# 5V_out_driver.net
KiCad netlist of a schematic drawn in Altium Designer
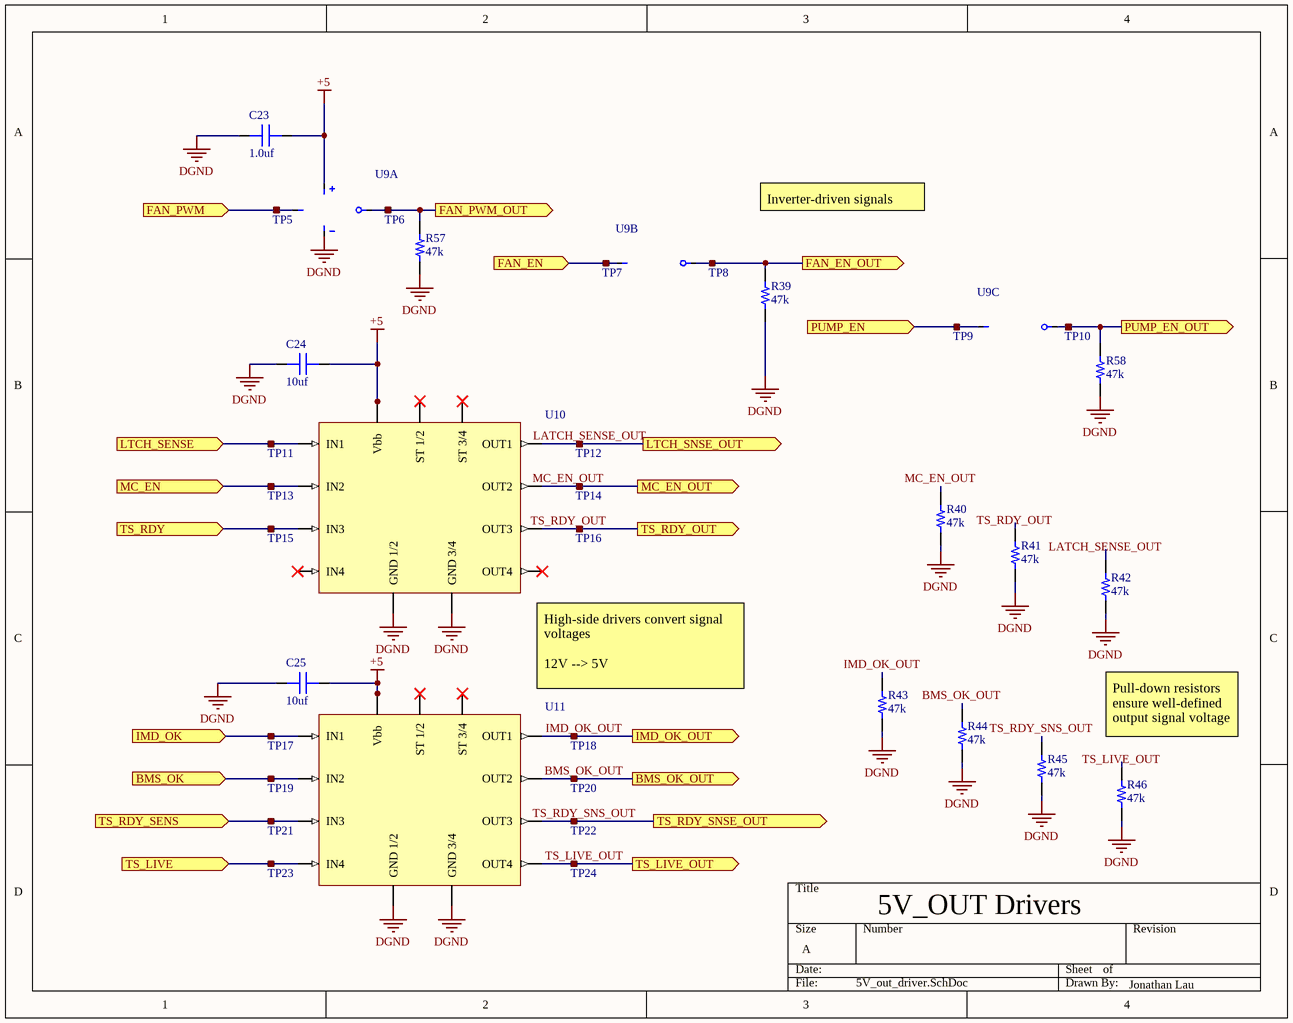
[diagram p0: 5V_out_driver.SchDoc]

(export (version "E")
  (design (tool "Eeschema 10.0.6"))
  (components
    (comp (ref "C23")
      (value "1.0uf")
      (footprint "CAP 0603/1608")
      (fields
        (field (name "Comment") "Capacitor MLCC 1.0uf 16V CAP 0603/1608")
        (field (name "CREATED_BY") "Nick Mah")
      )
      (libsource (lib "Altium-Lib") (part "Capacitor"))
    )
    (comp (ref "C24")
      (value "10uf")
      (footprint "CAP 0603/1608")
      (fields
        (field (name "Comment") "Capacitor MLCC 10uf 16V CAP 0603/1608")
        (field (name "CREATED_BY") "Nick Mah")
      )
      (libsource (lib "Altium-Lib") (part "Capacitor"))
    )
    (comp (ref "C25")
      (value "10uf")
      (footprint "CAP 0603/1608")
      (fields
        (field (name "Comment") "Capacitor MLCC 10uf 16V CAP 0603/1608")
        (field (name "CREATED_BY") "Nick Mah")
      )
      (libsource (lib "Altium-Lib") (part "Capacitor"))
    )
    (comp (ref "R39")
      (value "47k")
      (footprint "RES 0805/2012")
      (fields
        (field (name "TOLERANCE") "5%")
        (field (name "POWER") "1/4W")
        (field (name "Comment") "Resistor 47k 0805 1/4W 5%")
        (field (name "CREATED_BY") "Nick Mah")
      )
      (libsource (lib "Altium-Lib") (part "Resistor"))
    )
    (comp (ref "R40")
      (value "47k")
      (footprint "RES 0805/2012")
      (fields
        (field (name "TOLERANCE") "5%")
        (field (name "POWER") "1/4W")
        (field (name "Comment") "Resistor 47k 0805 1/4W 5%")
        (field (name "CREATED_BY") "Nick Mah")
      )
      (libsource (lib "Altium-Lib") (part "Resistor"))
    )
    (comp (ref "R41")
      (value "47k")
      (footprint "RES 0805/2012")
      (fields
        (field (name "TOLERANCE") "5%")
        (field (name "POWER") "1/4W")
        (field (name "Comment") "Resistor 47k 0805 1/4W 5%")
        (field (name "CREATED_BY") "Nick Mah")
      )
      (libsource (lib "Altium-Lib") (part "Resistor"))
    )
    (comp (ref "R42")
      (value "47k")
      (footprint "RES 0805/2012")
      (fields
        (field (name "TOLERANCE") "5%")
        (field (name "POWER") "1/4W")
        (field (name "Comment") "Resistor 47k 0805 1/4W 5%")
        (field (name "CREATED_BY") "Nick Mah")
      )
      (libsource (lib "Altium-Lib") (part "Resistor"))
    )
    (comp (ref "R43")
      (value "47k")
      (footprint "RES 0805/2012")
      (fields
        (field (name "TOLERANCE") "5%")
        (field (name "POWER") "1/4W")
        (field (name "Comment") "Resistor 47k 0805 1/4W 5%")
        (field (name "CREATED_BY") "Nick Mah")
      )
      (libsource (lib "Altium-Lib") (part "Resistor"))
    )
    (comp (ref "R44")
      (value "47k")
      (footprint "RES 0805/2012")
      (fields
        (field (name "TOLERANCE") "5%")
        (field (name "POWER") "1/4W")
        (field (name "Comment") "Resistor 47k 0805 1/4W 5%")
        (field (name "CREATED_BY") "Nick Mah")
      )
      (libsource (lib "Altium-Lib") (part "Resistor"))
    )
    (comp (ref "R45")
      (value "47k")
      (footprint "RES 0805/2012")
      (fields
        (field (name "TOLERANCE") "5%")
        (field (name "POWER") "1/4W")
        (field (name "Comment") "Resistor 47k 0805 1/4W 5%")
        (field (name "CREATED_BY") "Nick Mah")
      )
      (libsource (lib "Altium-Lib") (part "Resistor"))
    )
    (comp (ref "R46")
      (value "47k")
      (footprint "RES 0805/2012")
      (fields
        (field (name "TOLERANCE") "5%")
        (field (name "POWER") "1/4W")
        (field (name "Comment") "Resistor 47k 0805 1/4W 5%")
        (field (name "CREATED_BY") "Nick Mah")
      )
      (libsource (lib "Altium-Lib") (part "Resistor"))
    )
    (comp (ref "R57")
      (value "47k")
      (footprint "RES 0805/2012")
      (fields
        (field (name "TOLERANCE") "5%")
        (field (name "POWER") "1/4W")
        (field (name "Comment") "Resistor 47k 0805 1/4W 5%")
        (field (name "CREATED_BY") "Nick Mah")
      )
      (libsource (lib "Altium-Lib") (part "Resistor"))
    )
    (comp (ref "R58")
      (value "47k")
      (footprint "RES 0805/2012")
      (fields
        (field (name "TOLERANCE") "5%")
        (field (name "POWER") "1/4W")
        (field (name "Comment") "Resistor 47k 0805 1/4W 5%")
        (field (name "CREATED_BY") "Nick Mah")
      )
      (libsource (lib "Altium-Lib") (part "Resistor"))
    )
    (comp (ref "TP5") (value "RCU-0C") (footprint "RCU-0C") (libsource (lib "Altium-Lib") (part "RCU-0C")))
    (comp (ref "TP6") (value "RCU-0C") (footprint "RCU-0C") (libsource (lib "Altium-Lib") (part "RCU-0C")))
    (comp (ref "TP7") (value "RCU-0C") (footprint "RCU-0C") (libsource (lib "Altium-Lib") (part "RCU-0C")))
    (comp (ref "TP8") (value "RCU-0C") (footprint "RCU-0C") (libsource (lib "Altium-Lib") (part "RCU-0C")))
    (comp (ref "TP9") (value "RCU-0C") (footprint "RCU-0C") (libsource (lib "Altium-Lib") (part "RCU-0C")))
    (comp (ref "TP10") (value "RCU-0C") (footprint "RCU-0C") (libsource (lib "Altium-Lib") (part "RCU-0C")))
    (comp (ref "TP11") (value "RCU-0C") (footprint "RCU-0C") (libsource (lib "Altium-Lib") (part "RCU-0C")))
    (comp (ref "TP12") (value "RCU-0C") (footprint "RCU-0C") (libsource (lib "Altium-Lib") (part "RCU-0C")))
    (comp (ref "TP13") (value "RCU-0C") (footprint "RCU-0C") (libsource (lib "Altium-Lib") (part "RCU-0C")))
    (comp (ref "TP14") (value "RCU-0C") (footprint "RCU-0C") (libsource (lib "Altium-Lib") (part "RCU-0C")))
    (comp (ref "TP15") (value "RCU-0C") (footprint "RCU-0C") (libsource (lib "Altium-Lib") (part "RCU-0C")))
    (comp (ref "TP16") (value "RCU-0C") (footprint "RCU-0C") (libsource (lib "Altium-Lib") (part "RCU-0C")))
    (comp (ref "TP17") (value "RCU-0C") (footprint "RCU-0C") (libsource (lib "Altium-Lib") (part "RCU-0C")))
    (comp (ref "TP18") (value "RCU-0C") (footprint "RCU-0C") (libsource (lib "Altium-Lib") (part "RCU-0C")))
    (comp (ref "TP19") (value "RCU-0C") (footprint "RCU-0C") (libsource (lib "Altium-Lib") (part "RCU-0C")))
    (comp (ref "TP20") (value "RCU-0C") (footprint "RCU-0C") (libsource (lib "Altium-Lib") (part "RCU-0C")))
    (comp (ref "TP21") (value "RCU-0C") (footprint "RCU-0C") (libsource (lib "Altium-Lib") (part "RCU-0C")))
    (comp (ref "TP22") (value "RCU-0C") (footprint "RCU-0C") (libsource (lib "Altium-Lib") (part "RCU-0C")))
    (comp (ref "TP23") (value "RCU-0C") (footprint "RCU-0C") (libsource (lib "Altium-Lib") (part "RCU-0C")))
    (comp (ref "TP24") (value "RCU-0C") (footprint "RCU-0C") (libsource (lib "Altium-Lib") (part "RCU-0C")))
    (comp (ref "U9")
      (value "SN74LVC3G14DCUR")
      (footprint "R-PDSO-G8")
      (libsource (lib "Altium-Lib") (part "SN74LVC3G14DCUR"))
    )
    (comp (ref "U10")
      (value "PG-DSO-20")
      (footprint "PG-DSO-20")
      (description "High Side Driver")
      (fields (field (name "MFRPARTNO") "BTS716GXUMA1"))
      (libsource (lib "Altium-Lib") (part "BTS716G"))
    )
    (comp (ref "U11")
      (value "PG-DSO-20")
      (footprint "PG-DSO-20")
      (description "High Side Driver")
      (fields (field (name "MFRPARTNO") "BTS716GXUMA1"))
      (libsource (lib "Altium-Lib") (part "BTS716G"))
    )
  )
  (nets
    (net (code "1") (name "+5") (class "Default")
      (node (ref "C23") (pin "2") (pinfunction "2_2") (pintype "passive"))
      (node (ref "C24") (pin "1") (pinfunction "1_1") (pintype "passive"))
      (node (ref "C25") (pin "1") (pinfunction "1_1") (pintype "passive"))
      (node (ref "U10") (pin "1") (pinfunction "Vbb_1") (pintype "power_in"))
      (node (ref "U10") (pin "10") (pinfunction "Vbb_10") (pintype "power_in"))
      (node (ref "U10") (pin "11") (pinfunction "Vbb_11") (pintype "power_in"))
      (node (ref "U10") (pin "12") (pinfunction "Vbb_12") (pintype "power_in"))
      (node (ref "U10") (pin "15") (pinfunction "Vbb_15") (pintype "power_in"))
      (node (ref "U10") (pin "16") (pinfunction "Vbb_16") (pintype "power_in"))
      (node (ref "U10") (pin "19") (pinfunction "Vbb_19") (pintype "power_in"))
      (node (ref "U10") (pin "20") (pinfunction "Vbb_20") (pintype "power_in"))
      (node (ref "U11") (pin "1") (pinfunction "Vbb_1") (pintype "power_in"))
      (node (ref "U11") (pin "10") (pinfunction "Vbb_10") (pintype "power_in"))
      (node (ref "U11") (pin "11") (pinfunction "Vbb_11") (pintype "power_in"))
      (node (ref "U11") (pin "12") (pinfunction "Vbb_12") (pintype "power_in"))
      (node (ref "U11") (pin "15") (pinfunction "Vbb_15") (pintype "power_in"))
      (node (ref "U11") (pin "16") (pinfunction "Vbb_16") (pintype "power_in"))
      (node (ref "U11") (pin "19") (pinfunction "Vbb_19") (pintype "power_in"))
      (node (ref "U11") (pin "20") (pinfunction "Vbb_20") (pintype "power_in"))
      (node (ref "U9") (pin "8") (pinfunction "Vcc_8") (pintype "passive"))
    )
    (net (code "2") (name "/BMS_OK") (class "Default")
      (node (ref "TP19") (pin "1") (pintype "passive"))
      (node (ref "U11") (pin "5") (pinfunction "IN2_5") (pintype "input"))
    )
    (net (code "3") (name "/BMS_OK_OUT") (class "Default")
      (node (ref "R44") (pin "2") (pinfunction "2_2") (pintype "passive"))
      (node (ref "TP20") (pin "1") (pintype "passive"))
      (node (ref "U11") (pin "17") (pinfunction "OUT2_17") (pintype "output"))
    )
    (net (code "4") (name "/FAN_EN") (class "Default")
      (node (ref "TP7") (pin "1") (pintype "passive"))
      (node (ref "U9") (pin "3") (pinfunction "2A_3") (pintype "passive"))
    )
    (net (code "5") (name "/FAN_EN_OUT") (class "Default")
      (node (ref "R39") (pin "2") (pinfunction "2_2") (pintype "passive"))
      (node (ref "TP8") (pin "1") (pintype "passive"))
      (node (ref "U9") (pin "5") (pinfunction "2Y_5") (pintype "passive"))
    )
    (net (code "6") (name "/FAN_PWM") (class "Default")
      (node (ref "TP5") (pin "1") (pintype "passive"))
      (node (ref "U9") (pin "1") (pinfunction "1A_1") (pintype "passive"))
    )
    (net (code "7") (name "/FAN_PWM_OUT") (class "Default")
      (node (ref "R57") (pin "2") (pinfunction "2_2") (pintype "passive"))
      (node (ref "TP6") (pin "1") (pintype "passive"))
      (node (ref "U9") (pin "7") (pinfunction "1Y_7") (pintype "passive"))
    )
    (net (code "8") (name "/IMD_OK") (class "Default")
      (node (ref "TP17") (pin "1") (pintype "passive"))
      (node (ref "U11") (pin "3") (pinfunction "IN1_3") (pintype "input"))
    )
    (net (code "9") (name "/IMD_OK_OUT") (class "Default")
      (node (ref "R43") (pin "1") (pinfunction "1_1") (pintype "passive"))
      (node (ref "TP18") (pin "1") (pintype "passive"))
      (node (ref "U11") (pin "18") (pinfunction "OUT1_18") (pintype "output"))
    )
    (net (code "10") (name "/LATCH_SENSE_OUT") (class "Default")
      (node (ref "R42") (pin "2") (pinfunction "2_2") (pintype "passive"))
      (node (ref "TP12") (pin "1") (pintype "passive"))
      (node (ref "U10") (pin "18") (pinfunction "OUT1_18") (pintype "output"))
    )
    (net (code "11") (name "/LTCH_SENSE") (class "Default")
      (node (ref "TP11") (pin "1") (pintype "passive"))
      (node (ref "U10") (pin "3") (pinfunction "IN1_3") (pintype "input"))
    )
    (net (code "12") (name "/MC_EN") (class "Default")
      (node (ref "TP13") (pin "1") (pintype "passive"))
      (node (ref "U10") (pin "5") (pinfunction "IN2_5") (pintype "input"))
    )
    (net (code "13") (name "/MC_EN_OUT") (class "Default")
      (node (ref "R40") (pin "2") (pinfunction "2_2") (pintype "passive"))
      (node (ref "TP14") (pin "1") (pintype "passive"))
      (node (ref "U10") (pin "17") (pinfunction "OUT2_17") (pintype "output"))
    )
    (net (code "14") (name "/PUMP_EN") (class "Default")
      (node (ref "TP9") (pin "1") (pintype "passive"))
      (node (ref "U9") (pin "6") (pinfunction "3A_6") (pintype "passive"))
    )
    (net (code "15") (name "/PUMP_EN_OUT") (class "Default")
      (node (ref "R58") (pin "2") (pinfunction "2_2") (pintype "passive"))
      (node (ref "TP10") (pin "1") (pintype "passive"))
      (node (ref "U9") (pin "2") (pinfunction "3Y_2") (pintype "passive"))
    )
    (net (code "16") (name "/TS_LIVE") (class "Default")
      (node (ref "TP23") (pin "1") (pintype "passive"))
      (node (ref "U11") (pin "9") (pinfunction "IN4_9") (pintype "input"))
    )
    (net (code "17") (name "/TS_LIVE_OUT") (class "Default")
      (node (ref "R46") (pin "2") (pinfunction "2_2") (pintype "passive"))
      (node (ref "TP24") (pin "1") (pintype "passive"))
      (node (ref "U11") (pin "13") (pinfunction "OUT4_13") (pintype "output"))
    )
    (net (code "18") (name "/TS_RDY") (class "Default")
      (node (ref "TP15") (pin "1") (pintype "passive"))
      (node (ref "U10") (pin "7") (pinfunction "IN3_7") (pintype "input"))
    )
    (net (code "19") (name "/TS_RDY_OUT") (class "Default")
      (node (ref "R41") (pin "2") (pinfunction "2_2") (pintype "passive"))
      (node (ref "TP16") (pin "1") (pintype "passive"))
      (node (ref "U10") (pin "14") (pinfunction "OUT3_14") (pintype "output"))
    )
    (net (code "20") (name "/TS_RDY_SENS") (class "Default")
      (node (ref "TP21") (pin "1") (pintype "passive"))
      (node (ref "U11") (pin "7") (pinfunction "IN3_7") (pintype "input"))
    )
    (net (code "21") (name "/TS_RDY_SNS_OUT") (class "Default")
      (node (ref "R45") (pin "2") (pinfunction "2_2") (pintype "passive"))
      (node (ref "TP22") (pin "1") (pintype "passive"))
      (node (ref "U11") (pin "14") (pinfunction "OUT3_14") (pintype "output"))
    )
    (net (code "22") (name "DGND") (class "Default")
      (node (ref "C23") (pin "1") (pinfunction "1_1") (pintype "passive"))
      (node (ref "C24") (pin "2") (pinfunction "2_2") (pintype "passive"))
      (node (ref "C25") (pin "2") (pinfunction "2_2") (pintype "passive"))
      (node (ref "R39") (pin "1") (pinfunction "1_1") (pintype "passive"))
      (node (ref "R40") (pin "1") (pinfunction "1_1") (pintype "passive"))
      (node (ref "R41") (pin "1") (pinfunction "1_1") (pintype "passive"))
      (node (ref "R42") (pin "1") (pinfunction "1_1") (pintype "passive"))
      (node (ref "R43") (pin "2") (pinfunction "2_2") (pintype "passive"))
      (node (ref "R44") (pin "1") (pinfunction "1_1") (pintype "passive"))
      (node (ref "R45") (pin "1") (pinfunction "1_1") (pintype "passive"))
      (node (ref "R46") (pin "1") (pinfunction "1_1") (pintype "passive"))
      (node (ref "R57") (pin "1") (pinfunction "1_1") (pintype "passive"))
      (node (ref "R58") (pin "1") (pinfunction "1_1") (pintype "passive"))
      (node (ref "U10") (pin "2") (pinfunction "GND_1/2_2") (pintype "power_in"))
      (node (ref "U10") (pin "6") (pinfunction "GND_3/4_6") (pintype "power_in"))
      (node (ref "U11") (pin "2") (pinfunction "GND_1/2_2") (pintype "power_in"))
      (node (ref "U11") (pin "6") (pinfunction "GND_3/4_6") (pintype "power_in"))
      (node (ref "U9") (pin "4") (pinfunction "GND_4") (pintype "passive"))
    )
    (net (code "23") (name "unconnected-(U10-IN4-Pad9)") (class "Default")
      (node (ref "U10") (pin "9") (pinfunction "IN4_9") (pintype "input+no_connect"))
    )
    (net (code "24") (name "unconnected-(U10-OUT4-Pad13)") (class "Default")
      (node (ref "U10") (pin "13") (pinfunction "OUT4_13") (pintype "output+no_connect"))
    )
    (net (code "25") (name "unconnected-(U10-ST_1{slash}2-Pad4)") (class "Default")
      (node (ref "U10") (pin "4") (pinfunction "ST_1/2_4") (pintype "passive+no_connect"))
    )
    (net (code "26") (name "unconnected-(U10-ST_3{slash}4-Pad8)") (class "Default")
      (node (ref "U10") (pin "8") (pinfunction "ST_3/4_8") (pintype "passive+no_connect"))
    )
    (net (code "27") (name "unconnected-(U11-ST_1{slash}2-Pad4)") (class "Default")
      (node (ref "U11") (pin "4") (pinfunction "ST_1/2_4") (pintype "passive+no_connect"))
    )
    (net (code "28") (name "unconnected-(U11-ST_3{slash}4-Pad8)") (class "Default")
      (node (ref "U11") (pin "8") (pinfunction "ST_3/4_8") (pintype "passive+no_connect"))
    )
  )
)
